# Matherboard.net
KiCad netlist of a schematic drawn in Altium Designer
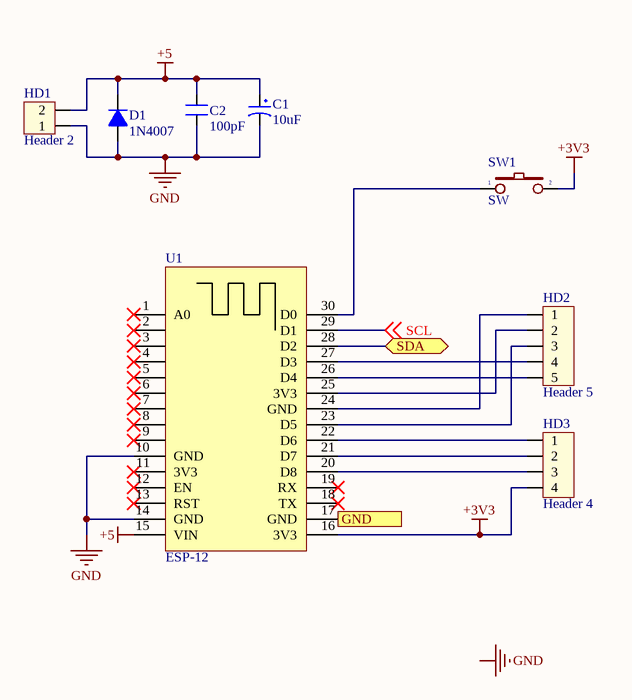
[diagram p0: Matherboard.SchDoc]

(export (version "E")
  (design (tool "Eeschema 10.0.6"))
  (components
    (comp (ref "C1")
      (value "10uF")
      (footprint "CP1/2")
      (description "Cap P  0,1uF < 22uF , 16 - 50V")
      (libsource (lib "hanguyen") (part "CP1"))
    )
    (comp (ref "C2")
      (value "100pF")
      (footprint "CN1")
      (description "Cap np  1pF - 472pF")
      (libsource (lib "hanguyen") (part "CN1"))
    )
    (comp (ref "D1")
      (value "1N4007")
      (footprint "SMA")
      (description "Diode 1A")
      (libsource (lib "hanguyen") (part "diode"))
    )
    (comp (ref "HD1")
      (value "Header 2")
      (footprint "HED2")
      (description "Header 2 (Green)")
      (libsource (lib "hanguyen") (part "Hed2"))
    )
    (comp (ref "HD2")
      (value "Header 5")
      (footprint "HED5 - KF270 - duplicate")
      (description "Header 5 (Green)")
      (libsource (lib "hanguyen") (part "Hed5"))
    )
    (comp (ref "HD3")
      (value "Header 4")
      (footprint "HED4")
      (description "Header 4 (Green)")
      (libsource (lib "hanguyen") (part "Hed4"))
    )
    (comp (ref "SW1")
      (value "SW")
      (footprint "SW2")
      (description "Switch button 2 pin")
      (libsource (lib "hanguyen") (part "SW2"))
    )
    (comp (ref "U1")
      (value "ESP-12")
      (footprint "Node MCU")
      (description "NodeMCU")
      (libsource (lib "hanguyen") (part "NodeMCU"))
    )
  )
  (nets
    (net (code "1") (name "+3V3") (class "Default")
      (node (ref "HD3") (pin "4") (pinfunction "4_4") (pintype "passive"))
      (node (ref "SW1") (pin "2") (pinfunction "2_2") (pintype "passive"))
      (node (ref "U1") (pin "16") (pinfunction "3V3_16") (pintype "passive"))
    )
    (net (code "2") (name "+5") (class "Default")
      (node (ref "C1") (pin "1") (pinfunction "1_1") (pintype "passive"))
      (node (ref "C2") (pin "2") (pinfunction "2_2") (pintype "passive"))
      (node (ref "D1") (pin "2") (pinfunction "K_2") (pintype "passive"))
      (node (ref "HD1") (pin "2") (pinfunction "2_2") (pintype "passive"))
      (node (ref "U1") (pin "15") (pinfunction "VIN_15") (pintype "passive"))
    )
    (net (code "3") (name "/SDA") (class "Default")
      (node (ref "U1") (pin "28") (pinfunction "D2_28") (pintype "passive"))
    )
    (net (code "4") (name "GND") (class "Default")
      (node (ref "C1") (pin "2") (pinfunction "2_2") (pintype "passive"))
      (node (ref "C2") (pin "1") (pinfunction "1_1") (pintype "passive"))
      (node (ref "D1") (pin "1") (pinfunction "A_1") (pintype "passive"))
      (node (ref "HD1") (pin "1") (pinfunction "1_1") (pintype "passive"))
      (node (ref "U1") (pin "10") (pinfunction "GND_10") (pintype "passive"))
      (node (ref "U1") (pin "14") (pinfunction "GND_14") (pintype "passive"))
    )
    (net (code "5") (name "Net-(HD2-Pad1)") (class "Default")
      (node (ref "HD2") (pin "1") (pinfunction "1_1") (pintype "passive"))
      (node (ref "U1") (pin "24") (pinfunction "GND_24") (pintype "passive"))
    )
    (net (code "6") (name "Net-(HD2-Pad2)") (class "Default")
      (node (ref "HD2") (pin "2") (pinfunction "2_2") (pintype "passive"))
      (node (ref "U1") (pin "25") (pinfunction "3V3_25") (pintype "passive"))
    )
    (net (code "7") (name "Net-(U1-D0)") (class "Default")
      (node (ref "SW1") (pin "1") (pinfunction "1_1") (pintype "passive"))
      (node (ref "U1") (pin "30") (pinfunction "D0_30") (pintype "passive"))
    )
    (net (code "8") (name "Net-(U1-D3)") (class "Default")
      (node (ref "HD2") (pin "4") (pinfunction "4_4") (pintype "passive"))
      (node (ref "U1") (pin "27") (pinfunction "D3_27") (pintype "passive"))
    )
    (net (code "9") (name "Net-(U1-D4)") (class "Default")
      (node (ref "HD2") (pin "5") (pinfunction "5_5") (pintype "passive"))
      (node (ref "U1") (pin "26") (pinfunction "D4_26") (pintype "passive"))
    )
    (net (code "10") (name "Net-(U1-D5)") (class "Default")
      (node (ref "HD2") (pin "3") (pinfunction "3_3") (pintype "passive"))
      (node (ref "U1") (pin "23") (pinfunction "D5_23") (pintype "passive"))
    )
    (net (code "11") (name "Net-(U1-D6)") (class "Default")
      (node (ref "HD3") (pin "1") (pinfunction "1_1") (pintype "passive"))
      (node (ref "U1") (pin "22") (pinfunction "D6_22") (pintype "passive"))
    )
    (net (code "12") (name "Net-(U1-D7)") (class "Default")
      (node (ref "HD3") (pin "2") (pinfunction "2_2") (pintype "passive"))
      (node (ref "U1") (pin "21") (pinfunction "D7_21") (pintype "passive"))
    )
    (net (code "13") (name "Net-(U1-D8)") (class "Default")
      (node (ref "HD3") (pin "3") (pinfunction "3_3") (pintype "passive"))
      (node (ref "U1") (pin "20") (pinfunction "D8_20") (pintype "passive"))
    )
    (net (code "14") (name "SCL") (class "Default")
      (node (ref "U1") (pin "29") (pinfunction "D1_29") (pintype "passive"))
    )
    (net (code "15") (name "unconnected-(U1-3V3-Pad11)") (class "Default")
      (node (ref "U1") (pin "11") (pinfunction "3V3_11") (pintype "passive+no_connect"))
    )
    (net (code "16") (name "unconnected-(U1-A0-Pad1)") (class "Default")
      (node (ref "U1") (pin "1") (pinfunction "A0_1") (pintype "passive+no_connect"))
    )
    (net (code "17") (name "unconnected-(U1-EN-Pad12)") (class "Default")
      (node (ref "U1") (pin "12") (pinfunction "EN_12") (pintype "passive+no_connect"))
    )
    (net (code "18") (name "unconnected-(U1-GND-Pad17)") (class "Default")
      (node (ref "U1") (pin "17") (pinfunction "GND_17") (pintype "passive"))
    )
    (net (code "19") (name "unconnected-(U1-Pad2)") (class "Default")
      (node (ref "U1") (pin "2") (pintype "passive+no_connect"))
    )
    (net (code "20") (name "unconnected-(U1-Pad3)") (class "Default")
      (node (ref "U1") (pin "3") (pintype "passive+no_connect"))
    )
    (net (code "21") (name "unconnected-(U1-Pad4)") (class "Default")
      (node (ref "U1") (pin "4") (pintype "passive+no_connect"))
    )
    (net (code "22") (name "unconnected-(U1-Pad5)") (class "Default")
      (node (ref "U1") (pin "5") (pintype "passive+no_connect"))
    )
    (net (code "23") (name "unconnected-(U1-Pad6)") (class "Default")
      (node (ref "U1") (pin "6") (pintype "passive+no_connect"))
    )
    (net (code "24") (name "unconnected-(U1-Pad7)") (class "Default")
      (node (ref "U1") (pin "7") (pintype "passive+no_connect"))
    )
    (net (code "25") (name "unconnected-(U1-Pad8)") (class "Default")
      (node (ref "U1") (pin "8") (pintype "passive+no_connect"))
    )
    (net (code "26") (name "unconnected-(U1-Pad9)") (class "Default")
      (node (ref "U1") (pin "9") (pintype "passive+no_connect"))
    )
    (net (code "27") (name "unconnected-(U1-RST-Pad13)") (class "Default")
      (node (ref "U1") (pin "13") (pinfunction "RST_13") (pintype "passive+no_connect"))
    )
    (net (code "28") (name "unconnected-(U1-RX-Pad19)") (class "Default")
      (node (ref "U1") (pin "19") (pinfunction "RX_19") (pintype "passive+no_connect"))
    )
    (net (code "29") (name "unconnected-(U1-TX-Pad18)") (class "Default")
      (node (ref "U1") (pin "18") (pinfunction "TX_18") (pintype "passive+no_connect"))
    )
  )
)
